# SolarSenseBoard.net
KiCad netlist of a schematic drawn in Altium Designer
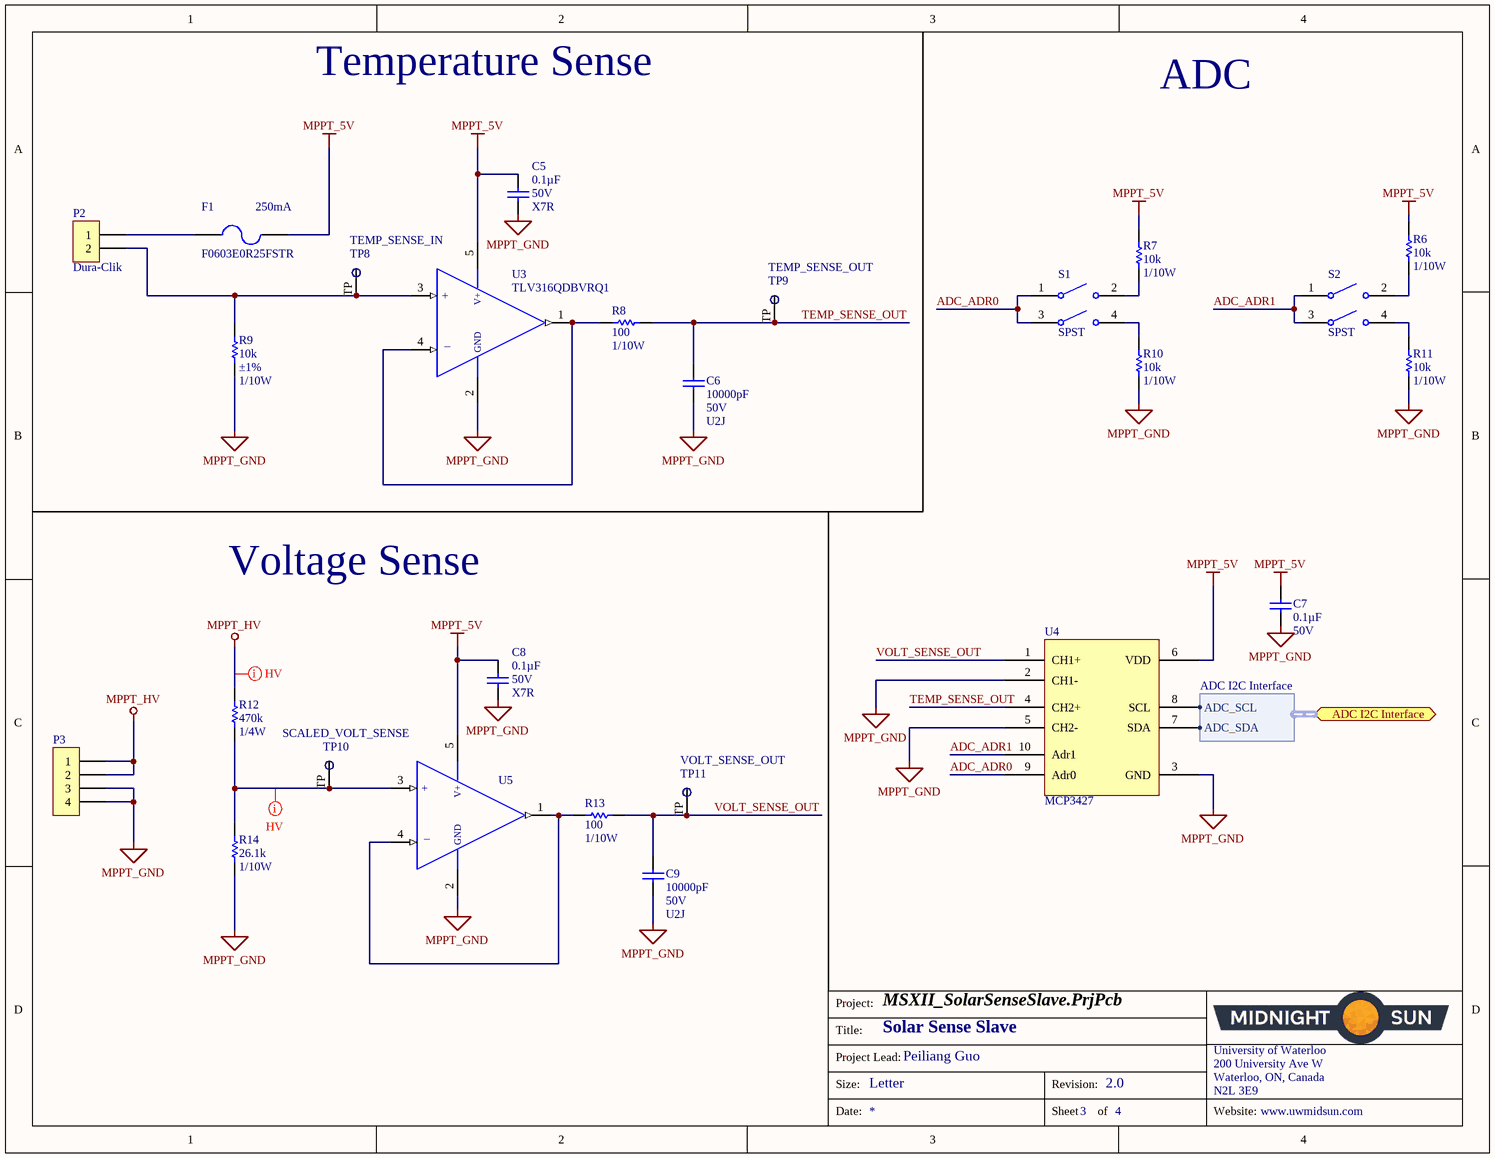
[diagram p0: SolarSenseBoard.SchDoc]

(export (version "E")
  (design (tool "Eeschema 10.0.6"))
  (components
    (comp (ref "C5")
      (value "CAP CER 0.1UF 50V 10% X7R 0603")
      (footprint "CAP, 0603")
      (description "0.10µF ±10% 50V Ceramic Capacitor X7R 0603 (1608 Metric)")
      (fields
        (field (name "TOLERANCE") "±10%")
        (field (name "CAPACITANCE") "0.1µF")
        (field (name "VOLTAGE") "50V")
        (field (name "TEMPERATURE COEFFICIENT") "X7R")
      )
      (libsource (lib "Schematic Diagrams") (part "CAP CER 0.1UF 50V 10% X7R 0603"))
    )
    (comp (ref "C6")
      (value "CAP CER 10nF 50V 5% X7R 0603")
      (footprint "CAP, 0603")
      (description "10000pF ±5% 50V Ceramic Capacitor U2J 0603 (1608 Metric)")
      (fields
        (field (name "TOLERANCE") "±5%")
        (field (name "CAPACITANCE") "10000pF")
        (field (name "VOLTAGE") "50V")
        (field (name "TEMPERATURE COEFFICIENT") "U2J")
      )
      (libsource (lib "Schematic Diagrams") (part "CAP CER 10nF 50V 5% X7R 0603"))
    )
    (comp (ref "C7")
      (value "CAP CER 0.1UF 50V 10% X7R 0603")
      (footprint "CAP, 0603")
      (description "0.10µF ±10% 50V Ceramic Capacitor X7R 0603 (1608 Metric)")
      (fields
        (field (name "TOLERANCE") "±10%")
        (field (name "CAPACITANCE") "0.1µF")
        (field (name "VOLTAGE") "50V")
      )
      (libsource (lib "Schematic Diagrams") (part "CAP CER 0.1UF 50V 10% X7R 0603"))
    )
    (comp (ref "C8")
      (value "CAP CER 0.1UF 50V 10% X7R 0603")
      (footprint "CAP, 0603")
      (description "0.10µF ±10% 50V Ceramic Capacitor X7R 0603 (1608 Metric)")
      (fields
        (field (name "TOLERANCE") "±10%")
        (field (name "CAPACITANCE") "0.1µF")
        (field (name "VOLTAGE") "50V")
        (field (name "TEMPERATURE COEFFICIENT") "X7R")
      )
      (libsource (lib "Schematic Diagrams") (part "CAP CER 0.1UF 50V 10% X7R 0603"))
    )
    (comp (ref "C9")
      (value "CAP CER 10nF 50V 5% X7R 0603")
      (footprint "CAP, 0603")
      (description "10000pF ±5% 50V Ceramic Capacitor U2J 0603 (1608 Metric)")
      (fields
        (field (name "TOLERANCE") "±5%")
        (field (name "CAPACITANCE") "10000pF")
        (field (name "VOLTAGE") "50V")
        (field (name "TEMPERATURE COEFFICIENT") "U2J")
      )
      (libsource (lib "Schematic Diagrams") (part "CAP CER 10nF 50V 5% X7R 0603"))
    )
    (comp (ref "F1")
      (value "FUSE 250MA 32VDC 0603")
      (footprint "RES, 0603")
      (fields
        (field (name "MANUFACTURER") "Kyocera AVX")
        (field (name "MANUFACTURER PART NUMBER") "F0603E0R25FSTR")
        (field (name "FUSE CURRENT") "250mA")
      )
      (libsource (lib "Schematic Diagrams") (part "FUSE 250MA 32VDC 0603"))
    )
    (comp (ref "P2")
      (value "Dura-Clik")
      (footprint "CONN, 2POS Dura-Click Vertical")
      (description "2 Positions Header, Shrouded Connector 0.079\" (2.00mm) Surface Mount, Vertical Tin")
      (fields
        (field (name "MANUFACTURER") "Molex, LLC")
        (field (name "MANUFACTURER PART NUMBER") "5600200220")
      )
      (libsource (lib "Schematic Diagrams") (part "CONN 2POS DURA-CLIK 0.079{dblquote} VERT"))
    )
    (comp (ref "P3")
      (value "CONN 4POS MX150L")
      (footprint "CONN, 4POS MX150L")
      (description "Connector Header Panel Mount, Through Hole, Right Angle 4 position 0.230\" (5.84mm)")
      (libsource (lib "Schematic Diagrams") (part "CONN 4POS MX150L"))
    )
    (comp (ref "R6")
      (value "RES 10K OHM 1% 1/10W 0603")
      (footprint "RES, 0603")
      (description "RES SMD 10K OHM 1% 1/10W 0603")
      (fields
        (field (name "TOLERANCE") "±1%")
        (field (name "RESISTANCE") "10k")
        (field (name "POWER") "1/10W")
      )
      (libsource (lib "Schematic Diagrams") (part "RES 10K OHM 1% 1/10W 0603"))
    )
    (comp (ref "R7")
      (value "RES 10K OHM 1% 1/10W 0603")
      (footprint "RES, 0603")
      (description "RES SMD 10K OHM 1% 1/10W 0603")
      (fields
        (field (name "TOLERANCE") "±1%")
        (field (name "RESISTANCE") "10k")
        (field (name "POWER") "1/10W")
      )
      (libsource (lib "Schematic Diagrams") (part "RES 10K OHM 1% 1/10W 0603"))
    )
    (comp (ref "R8")
      (value "RES 100 OHM 1% 1/10W 0603")
      (footprint "RES, 0603")
      (description "100 Ohm ±1% 0.1W, 1/10W Chip Resistor 0603 (1608 Metric) Moisture Resistant Thick Film")
      (fields
        (field (name "TOLERANCE") "±1%")
        (field (name "RESISTANCE") "100")
        (field (name "POWER") "1/10W")
      )
      (libsource (lib "Schematic Diagrams") (part "RES 100 OHM 1% 1/10W 0603"))
    )
    (comp (ref "R9")
      (value "RES 10K OHM 1% 1/10W 0603")
      (footprint "RES, 0603")
      (description "RES SMD 10K OHM 1% 1/10W 0603")
      (fields
        (field (name "RESISTANCE") "10k")
        (field (name "TOLERANCE") "±1%")
        (field (name "POWER") "1/10W")
      )
      (libsource (lib "Schematic Diagrams") (part "RES 10K OHM 1% 1/10W 0603"))
    )
    (comp (ref "R10")
      (value "RES 10K OHM 1% 1/10W 0603")
      (footprint "RES, 0603")
      (description "RES SMD 10K OHM 1% 1/10W 0603")
      (fields
        (field (name "TOLERANCE") "±1%")
        (field (name "RESISTANCE") "10k")
        (field (name "POWER") "1/10W")
      )
      (libsource (lib "Schematic Diagrams") (part "RES 10K OHM 1% 1/10W 0603"))
    )
    (comp (ref "R11")
      (value "RES 10K OHM 1% 1/10W 0603")
      (footprint "RES, 0603")
      (description "RES SMD 10K OHM 1% 1/10W 0603")
      (fields
        (field (name "TOLERANCE") "±1%")
        (field (name "RESISTANCE") "10k")
        (field (name "POWER") "1/10W")
      )
      (libsource (lib "Schematic Diagrams") (part "RES 10K OHM 1% 1/10W 0603"))
    )
    (comp (ref "R12")
      (value "RES 470K OHM 1% 1/4W 0603")
      (footprint "RES, 0603")
      (description "RES SMD 470K OHM 1% 1/4W 0603")
      (fields
        (field (name "TOLERANCE") "±1%")
        (field (name "RESISTANCE") "470k")
        (field (name "POWER") "1/4W")
      )
      (libsource (lib "Schematic Diagrams") (part "RES 470K OHM 1% 1/4W 0603"))
    )
    (comp (ref "R13")
      (value "RES 100 OHM 1% 1/10W 0603")
      (footprint "RES, 0603")
      (description "100 Ohm ±1% 0.1W, 1/10W Chip Resistor 0603 (1608 Metric) Moisture Resistant Thick Film")
      (fields
        (field (name "TOLERANCE") "±1%")
        (field (name "RESISTANCE") "100")
        (field (name "POWER") "1/10W")
      )
      (libsource (lib "Schematic Diagrams") (part "RES 100 OHM 1% 1/10W 0603"))
    )
    (comp (ref "R14")
      (value "RES 26.1K OHM 1% 1/10W 0603")
      (footprint "RES, 0603")
      (description "RES SMD 26.1K OHM 1% 1/10W 0603")
      (fields
        (field (name "TOLERANCE") "±1%")
        (field (name "RESISTANCE") "26.1k")
        (field (name "POWER") "1/10W")
      )
      (libsource (lib "Schematic Diagrams") (part "RES 26.1K OHM 1% 1/10W 0603"))
    )
    (comp (ref "S1")
      (value "SPST")
      (footprint "SW SPST 2POS DIP 0.1A 20V")
      (description "SWITCH SLIDE DIP SPST 100MA 20V")
      (fields
        (field (name "MANUFACTURER") "CTS Electrocomponents")
        (field (name "MANUFACTURER PART NUMBER") "219-2MST")
      )
      (libsource (lib "Schematic Diagrams") (part "SW SPST 2POS DIP 0.1A 20V"))
    )
    (comp (ref "S2")
      (value "SPST")
      (footprint "SW SPST 2POS DIP 0.1A 20V")
      (description "SWITCH SLIDE DIP SPST 100MA 20V")
      (fields
        (field (name "MANUFACTURER") "CTS Electrocomponents")
        (field (name "MANUFACTURER PART NUMBER") "219-2MST")
      )
      (libsource (lib "Schematic Diagrams") (part "SW SPST 2POS DIP 0.1A 20V"))
    )
    (comp (ref "TP8")
      (value "TEMP_SENSE_IN")
      (footprint "Test Point")
      (libsource (lib "Schematic Diagrams") (part "Test Point"))
    )
    (comp (ref "TP9")
      (value "TEMP_SENSE_OUT")
      (footprint "Test Point")
      (libsource (lib "Schematic Diagrams") (part "Test Point"))
    )
    (comp (ref "TP10")
      (value "SCALED_VOLT_SENSE")
      (footprint "Test Point")
      (libsource (lib "Schematic Diagrams") (part "Test Point"))
    )
    (comp (ref "TP11")
      (value "VOLT_SENSE_OUT")
      (footprint "Test Point")
      (libsource (lib "Schematic Diagrams") (part "Test Point"))
    )
    (comp (ref "U3")
      (value "IC OP AMP GEN PURPOSE RR 10MHZ SOT-23-5")
      (footprint "IC OP AMP GP RR 10MHZ SOT-23-5")
      (description "General Purpose Amplifier 1 Circuit Rail-to-Rail SOT-23-5")
      (fields (field (name "MANUFACTURER PART NUMBER 1") "TLV316QDBVRQ1"))
      (libsource (lib "Schematic Diagrams") (part "IC OP AMP GEN PURPOSE RR 10MHZ SOT-23-5"))
    )
    (comp (ref "U4")
      (value "IC ADC MCP3427 10MSOP")
      (footprint "IC ADC MCP3427")
      (description "16 Bit Analog to Digital Converter 2 Input 1 Sigma-Delta 10-MSOP")
      (fields
        (field (name "MANUFACTURER") "Microchip Technology")
        (field (name "MANUFACTURER PART NUMBER") "MCP3427-E/UN")
        (field (name "BASE PART NUMBER") "MCP3427")
      )
      (libsource (lib "Schematic Diagrams") (part "IC ADC MCP3427 10MSOP"))
    )
    (comp (ref "U5")
      (value "IC OP AMP GEN PURPOSE RR 10MHZ SOT-23-5")
      (footprint "IC OP AMP GP RR 10MHZ SOT-23-5")
      (description "General Purpose Amplifier 1 Circuit Rail-to-Rail SOT-23-5")
      (libsource (lib "Schematic Diagrams") (part "IC OP AMP GEN PURPOSE RR 10MHZ SOT-23-5"))
    )
  )
  (nets
    (net (code "4") (name "/ADC_ADR0") (class "Default")
      (node (ref "S1") (pin "1") (pinfunction "1_1") (pintype "passive"))
      (node (ref "S1") (pin "3") (pinfunction "3_3") (pintype "passive"))
      (node (ref "U4") (pin "9") (pinfunction "Adr0_9") (pintype "passive"))
    )
    (net (code "5") (name "/ADC_ADR1") (class "Default")
      (node (ref "S2") (pin "1") (pinfunction "1_1") (pintype "passive"))
      (node (ref "S2") (pin "3") (pinfunction "3_3") (pintype "passive"))
      (node (ref "U4") (pin "10") (pinfunction "Adr1_10") (pintype "passive"))
    )
    (net (code "6") (name "/ADC_SCL") (class "Default")
      (node (ref "U4") (pin "8") (pinfunction "SCL_8") (pintype "passive"))
    )
    (net (code "7") (name "/ADC_SDA") (class "Default")
      (node (ref "U4") (pin "7") (pinfunction "SDA_7") (pintype "passive"))
    )
    (net (code "8") (name "/TEMP_SENSE_OUT") (class "Default")
      (node (ref "C6") (pin "1") (pinfunction "1_1") (pintype "passive"))
      (node (ref "R8") (pin "2") (pinfunction "2_2") (pintype "passive"))
      (node (ref "TP9") (pin "TP") (pinfunction "1_TP") (pintype "passive"))
      (node (ref "U4") (pin "4") (pinfunction "CH2+_4") (pintype "passive"))
    )
    (net (code "9") (name "/VOLT_SENSE_OUT") (class "Default")
      (node (ref "C9") (pin "1") (pinfunction "1_1") (pintype "passive"))
      (node (ref "R13") (pin "2") (pinfunction "2_2") (pintype "passive"))
      (node (ref "TP11") (pin "TP") (pinfunction "1_TP") (pintype "passive"))
      (node (ref "U4") (pin "1") (pinfunction "CH1+_1") (pintype "passive"))
    )
    (net (code "11") (name "MPPT_5V") (class "Default")
      (node (ref "C5") (pin "1") (pinfunction "1_1") (pintype "passive"))
      (node (ref "C7") (pin "1") (pinfunction "1_1") (pintype "passive"))
      (node (ref "C8") (pin "1") (pinfunction "1_1") (pintype "passive"))
      (node (ref "F1") (pin "2") (pinfunction "2_2") (pintype "passive"))
      (node (ref "R6") (pin "1") (pinfunction "1_1") (pintype "passive"))
      (node (ref "R7") (pin "1") (pinfunction "1_1") (pintype "passive"))
      (node (ref "U3") (pin "5") (pinfunction "VDD_5") (pintype "power_in"))
      (node (ref "U4") (pin "6") (pinfunction "VDD_6") (pintype "passive"))
      (node (ref "U5") (pin "5") (pinfunction "VDD_5") (pintype "power_in"))
    )
    (net (code "12") (name "MPPT_GND") (class "Default")
      (node (ref "C5") (pin "2") (pinfunction "2_2") (pintype "passive"))
      (node (ref "C6") (pin "2") (pinfunction "2_2") (pintype "passive"))
      (node (ref "C7") (pin "2") (pinfunction "2_2") (pintype "passive"))
      (node (ref "C8") (pin "2") (pinfunction "2_2") (pintype "passive"))
      (node (ref "C9") (pin "2") (pinfunction "2_2") (pintype "passive"))
      (node (ref "P3") (pin "3") (pinfunction "3_3") (pintype "passive"))
      (node (ref "P3") (pin "4") (pinfunction "4_4") (pintype "passive"))
      (node (ref "R10") (pin "2") (pinfunction "2_2") (pintype "passive"))
      (node (ref "R11") (pin "2") (pinfunction "2_2") (pintype "passive"))
      (node (ref "R14") (pin "2") (pinfunction "2_2") (pintype "passive"))
      (node (ref "R9") (pin "2") (pinfunction "2_2") (pintype "passive"))
      (node (ref "U3") (pin "2") (pinfunction "VSS_2") (pintype "power_in"))
      (node (ref "U4") (pin "2") (pinfunction "CH1-_2") (pintype "passive"))
      (node (ref "U4") (pin "3") (pinfunction "GND_3") (pintype "passive"))
      (node (ref "U4") (pin "5") (pinfunction "CH2-_5") (pintype "passive"))
      (node (ref "U5") (pin "2") (pinfunction "VSS_2") (pintype "power_in"))
    )
    (net (code "13") (name "MPPT_HV") (class "Default")
      (node (ref "P3") (pin "1") (pinfunction "1_1") (pintype "passive"))
      (node (ref "P3") (pin "2") (pinfunction "2_2") (pintype "passive"))
      (node (ref "R12") (pin "1") (pinfunction "1_1") (pintype "passive"))
    )
    (net (code "14") (name "Net-(F1-Pad1)") (class "Default")
      (node (ref "F1") (pin "1") (pinfunction "1_1") (pintype "passive"))
      (node (ref "P2") (pin "1") (pinfunction "1_1") (pintype "passive"))
    )
    (net (code "15") (name "Net-(R6-Pad2)") (class "Default")
      (node (ref "R6") (pin "2") (pinfunction "2_2") (pintype "passive"))
      (node (ref "S2") (pin "2") (pinfunction "2_2") (pintype "passive"))
    )
    (net (code "16") (name "Net-(R7-Pad2)") (class "Default")
      (node (ref "R7") (pin "2") (pinfunction "2_2") (pintype "passive"))
      (node (ref "S1") (pin "2") (pinfunction "2_2") (pintype "passive"))
    )
    (net (code "17") (name "Net-(R10-Pad1)") (class "Default")
      (node (ref "R10") (pin "1") (pinfunction "1_1") (pintype "passive"))
      (node (ref "S1") (pin "4") (pinfunction "4_4") (pintype "passive"))
    )
    (net (code "18") (name "Net-(R11-Pad1)") (class "Default")
      (node (ref "R11") (pin "1") (pinfunction "1_1") (pintype "passive"))
      (node (ref "S2") (pin "4") (pinfunction "4_4") (pintype "passive"))
    )
    (net (code "19") (name "Net-(TP8-1)") (class "Default")
      (node (ref "P2") (pin "2") (pinfunction "2_2") (pintype "passive"))
      (node (ref "R9") (pin "1") (pinfunction "1_1") (pintype "passive"))
      (node (ref "TP8") (pin "TP") (pinfunction "1_TP") (pintype "passive"))
      (node (ref "U3") (pin "3") (pinfunction "+IN_3") (pintype "input"))
    )
    (net (code "20") (name "Net-(TP10-1)") (class "Default")
      (node (ref "R12") (pin "2") (pinfunction "2_2") (pintype "passive"))
      (node (ref "R14") (pin "1") (pinfunction "1_1") (pintype "passive"))
      (node (ref "TP10") (pin "TP") (pinfunction "1_TP") (pintype "passive"))
      (node (ref "U5") (pin "3") (pinfunction "+IN_3") (pintype "input"))
    )
    (net (code "21") (name "Net-(U3--IN)") (class "Default")
      (node (ref "R8") (pin "1") (pinfunction "1_1") (pintype "passive"))
      (node (ref "U3") (pin "1") (pinfunction "OUTPUT_1") (pintype "output"))
      (node (ref "U3") (pin "4") (pinfunction "-IN_4") (pintype "input"))
    )
    (net (code "22") (name "Net-(U5--IN)") (class "Default")
      (node (ref "R13") (pin "1") (pinfunction "1_1") (pintype "passive"))
      (node (ref "U5") (pin "1") (pinfunction "OUTPUT_1") (pintype "output"))
      (node (ref "U5") (pin "4") (pinfunction "-IN_4") (pintype "input"))
    )
  )
)
